# FPGA.net
KiCad netlist of a schematic drawn in Altium Designer
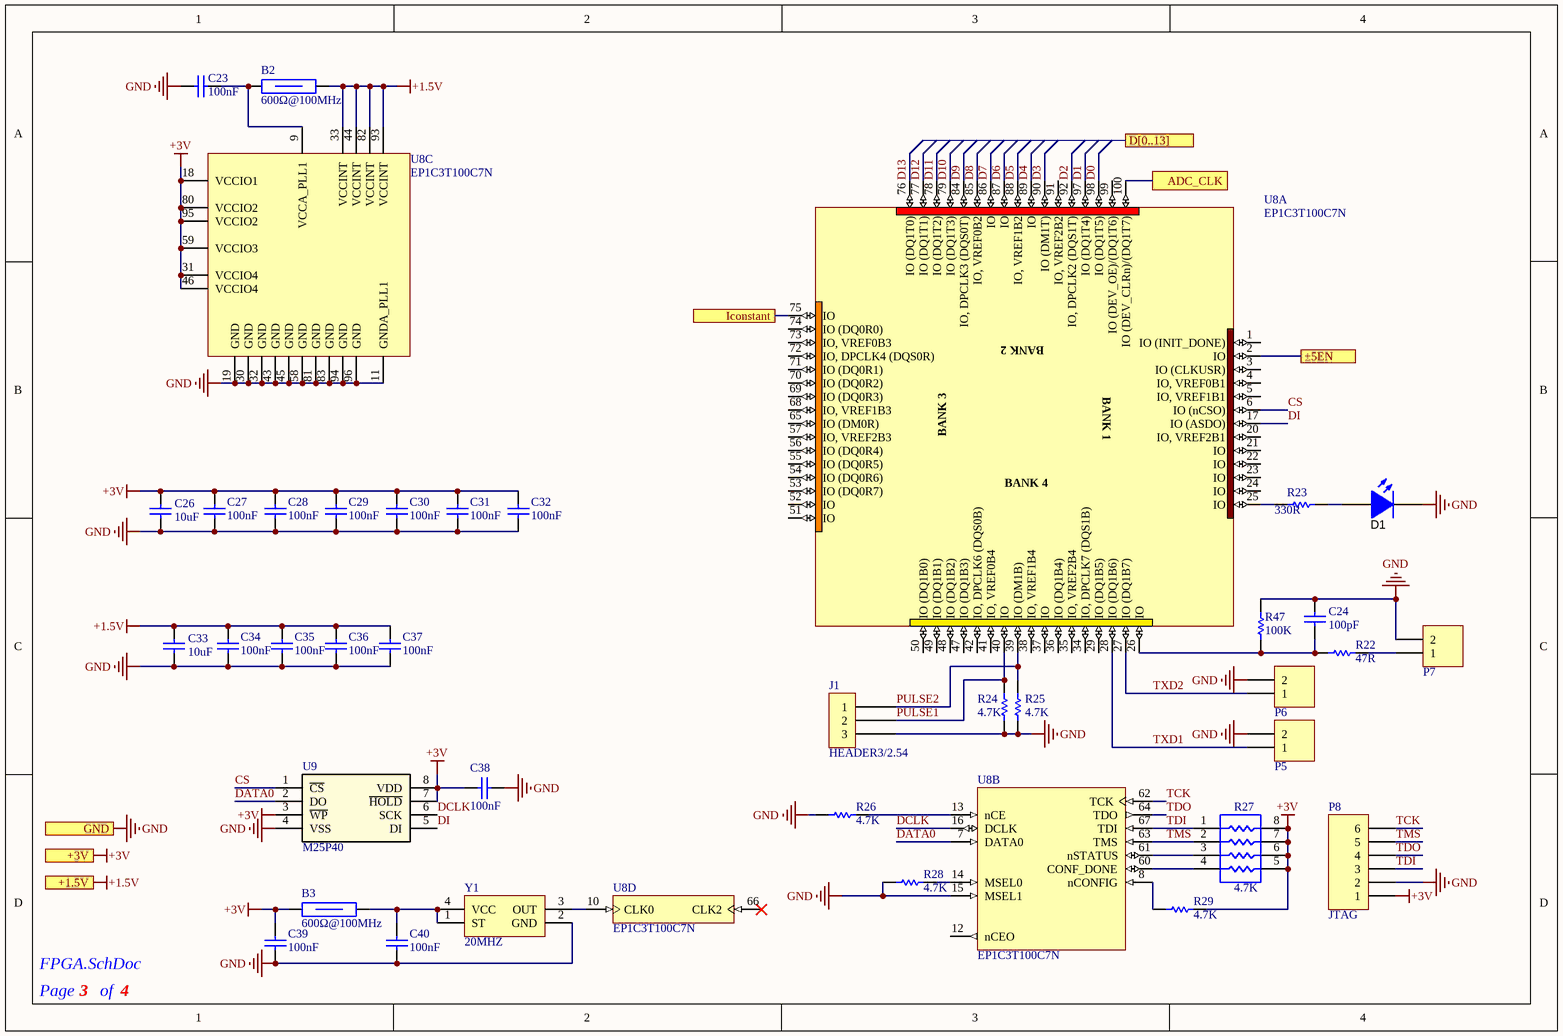
[diagram p0: FPGA.SchDoc]

(export (version "E")
  (design (tool "Eeschema 10.0.6"))
  (components
    (comp (ref "B2")
      (value "600Ω@100MHz")
      (footprint "R0805_L")
      (description "600Ω @ 100MHz \r\n线路数 1 \r\n额定电流（最大） 600mA \r\n直流电阻（DCR）（最大） 210mΩ")
      (libsource (lib "00Lib") (part "600Ω@100MHz"))
    )
    (comp (ref "B3")
      (value "600Ω@100MHz")
      (footprint "R0805_L")
      (description "600Ω @ 100MHz \r\n线路数 1 \r\n额定电流（最大） 600mA \r\n直流电阻（DCR）（最大） 210mΩ")
      (libsource (lib "00Lib") (part "600Ω@100MHz"))
    )
    (comp (ref "C23")
      (value "100nF")
      (footprint "R0603_C")
      (description "精度 ±10% \r\n容值 100nF \r\n额定电压 50V \r\n温漂系数（介质材料) X7R")
      (libsource (lib "00Lib") (part "100nF/0603/50V"))
    )
    (comp (ref "C24")
      (value "100pF")
      (footprint "R0603_C")
      (description "精度 ±5% \r\n容值 100pF \r\n额定电压 50V \r\n温漂系数（介质材料) C0G")
      (libsource (lib "00Lib") (part "100pF/0603/50V"))
    )
    (comp (ref "C26")
      (value "10uF")
      (footprint "R0805_C")
      (description "精度 ±10% \r\n容值 10uF \r\n额定电压 16V \r\n温漂系数（介质材料) X7R")
      (libsource (lib "00Lib") (part "10uF/0805/16V"))
    )
    (comp (ref "C27")
      (value "100nF")
      (footprint "R0603_C")
      (description "精度 ±10% \r\n容值 100nF \r\n额定电压 50V \r\n温漂系数（介质材料) X7R")
      (libsource (lib "00Lib") (part "100nF/0603/50V"))
    )
    (comp (ref "C28")
      (value "100nF")
      (footprint "R0603_C")
      (description "精度 ±10% \r\n容值 100nF \r\n额定电压 50V \r\n温漂系数（介质材料) X7R")
      (libsource (lib "00Lib") (part "100nF/0603/50V"))
    )
    (comp (ref "C29")
      (value "100nF")
      (footprint "R0603_C")
      (description "精度 ±10% \r\n容值 100nF \r\n额定电压 50V \r\n温漂系数（介质材料) X7R")
      (libsource (lib "00Lib") (part "100nF/0603/50V"))
    )
    (comp (ref "C30")
      (value "100nF")
      (footprint "R0603_C")
      (description "精度 ±10% \r\n容值 100nF \r\n额定电压 50V \r\n温漂系数（介质材料) X7R")
      (libsource (lib "00Lib") (part "100nF/0603/50V"))
    )
    (comp (ref "C31")
      (value "100nF")
      (footprint "R0603_C")
      (description "精度 ±10% \r\n容值 100nF \r\n额定电压 50V \r\n温漂系数（介质材料) X7R")
      (libsource (lib "00Lib") (part "100nF/0603/50V"))
    )
    (comp (ref "C32")
      (value "100nF")
      (footprint "R0603_C")
      (description "精度 ±10% \r\n容值 100nF \r\n额定电压 50V \r\n温漂系数（介质材料) X7R")
      (libsource (lib "00Lib") (part "100nF/0603/50V"))
    )
    (comp (ref "C33")
      (value "10uF")
      (footprint "R0805_C")
      (description "精度 ±10% \r\n容值 10uF \r\n额定电压 16V \r\n温漂系数（介质材料) X7R")
      (libsource (lib "00Lib") (part "10uF/0805/16V"))
    )
    (comp (ref "C34")
      (value "100nF")
      (footprint "R0603_C")
      (description "精度 ±10% \r\n容值 100nF \r\n额定电压 50V \r\n温漂系数（介质材料) X7R")
      (libsource (lib "00Lib") (part "100nF/0603/50V"))
    )
    (comp (ref "C35")
      (value "100nF")
      (footprint "R0603_C")
      (description "精度 ±10% \r\n容值 100nF \r\n额定电压 50V \r\n温漂系数（介质材料) X7R")
      (libsource (lib "00Lib") (part "100nF/0603/50V"))
    )
    (comp (ref "C36")
      (value "100nF")
      (footprint "R0603_C")
      (description "精度 ±10% \r\n容值 100nF \r\n额定电压 50V \r\n温漂系数（介质材料) X7R")
      (libsource (lib "00Lib") (part "100nF/0603/50V"))
    )
    (comp (ref "C37")
      (value "100nF")
      (footprint "R0603_C")
      (description "精度 ±10% \r\n容值 100nF \r\n额定电压 50V \r\n温漂系数（介质材料) X7R")
      (libsource (lib "00Lib") (part "100nF/0603/50V"))
    )
    (comp (ref "C38")
      (value "100nF")
      (footprint "R0603_C")
      (description "精度 ±10% \r\n容值 100nF \r\n额定电压 50V \r\n温漂系数（介质材料) X7R")
      (libsource (lib "00Lib") (part "100nF/0603/50V"))
    )
    (comp (ref "C39")
      (value "100nF")
      (footprint "R0603_C")
      (description "精度 ±10% \r\n容值 100nF \r\n额定电压 50V \r\n温漂系数（介质材料) X7R")
      (libsource (lib "00Lib") (part "100nF/0603/50V"))
    )
    (comp (ref "C40")
      (value "100nF")
      (footprint "R0603_C")
      (description "精度 ±10% \r\n容值 100nF \r\n额定电压 50V \r\n温漂系数（介质材料) X7R")
      (libsource (lib "00Lib") (part "100nF/0603/50V"))
    )
    (comp (ref "D1")
      (value "MHT192WDT-C2")
      (footprint "LED_0603_RED")
      (libsource (lib "00") (part "MHT192WDT-C2"))
    )
    (comp (ref "J1")
      (value "HEADER3/2.54")
      (footprint "SIP3/2.54")
      (description "3pin,单排,2.54mm间距")
      (libsource (lib "00Lib") (part "HEADER3/2.54"))
    )
    (comp (ref "P5")
      (value "Header 2")
      (footprint "CP1X2")
      (description "Header, 2-Pin")
      (libsource (lib "00Lib") (part "Header 2"))
    )
    (comp (ref "P6")
      (value "Header 2")
      (footprint "CP1X2")
      (description "Header, 2-Pin")
      (libsource (lib "00Lib") (part "Header 2"))
    )
    (comp (ref "P7")
      (value "Header 2")
      (footprint "CP1X2")
      (description "Header, 2-Pin")
      (libsource (lib "00Lib") (part "Header 2"))
    )
    (comp (ref "P8")
      (value "JTAG")
      (footprint "CP1X6")
      (description "Header, 6-Pin")
      (libsource (lib "00Lib") (part "Header 6"))
    )
    (comp (ref "R22")
      (value "47R")
      (footprint "R0603_R")
      (description "精度 ±1% \r\n温度系数 ±100ppm/℃ \r\n阻值 47Ω \r\n功率 0.1W")
      (libsource (lib "00Lib") (part "47R/0603"))
    )
    (comp (ref "R23")
      (value "330R")
      (footprint "R0603_R")
      (description "精度 ±1% \r\n温度系数 ±100ppm/℃ \r\n阻值 330Ω \r\n功率 0.1W")
      (libsource (lib "00Lib") (part "330R/0603"))
    )
    (comp (ref "R24")
      (value "4.7K")
      (footprint "R0603_R")
      (description "精度 ±1% \r\n阻值 4.7kΩ \r\n温度系数 ±100ppm/℃ \r\n功率 0.1W")
      (libsource (lib "00Lib") (part "4.7K/0603"))
    )
    (comp (ref "R25")
      (value "4.7K")
      (footprint "R0603_R")
      (description "精度 ±1% \r\n阻值 4.7kΩ \r\n温度系数 ±100ppm/℃ \r\n功率 0.1W")
      (libsource (lib "00Lib") (part "4.7K/0603"))
    )
    (comp (ref "R26")
      (value "4.7K")
      (footprint "R0603_R")
      (description "精度 ±1% \r\n阻值 4.7kΩ \r\n温度系数 ±100ppm/℃ \r\n功率 0.1W")
      (libsource (lib "00Lib") (part "4.7K/0603"))
    )
    (comp (ref "R27")
      (value "4.7K")
      (footprint "R0603X4")
      (description "4.7K \r\n电阻器数 4 \r\n精度 ±1% \r\n安装类型 表面贴装 \r\n每元件功率 1/16W \r\n温度系数 ±200ppm/℃")
      (libsource (lib "00Lib") (part "4.7K/0603X4"))
    )
    (comp (ref "R28")
      (value "4.7K")
      (footprint "R0603_R")
      (description "精度 ±1% \r\n阻值 4.7kΩ \r\n温度系数 ±100ppm/℃ \r\n功率 0.1W")
      (libsource (lib "00Lib") (part "4.7K/0603"))
    )
    (comp (ref "R29")
      (value "4.7K")
      (footprint "R0603_R")
      (description "精度 ±1% \r\n阻值 4.7kΩ \r\n温度系数 ±100ppm/℃ \r\n功率 0.1W")
      (libsource (lib "00Lib") (part "4.7K/0603"))
    )
    (comp (ref "R47")
      (value "100K")
      (footprint "R0603_R")
      (description "精度 ±1% \r\n阻值 100kΩ \r\n温度系数 ±100ppm/℃ \r\n功率 0.1W")
      (libsource (lib "00Lib") (part "100K/0603"))
    )
    (comp (ref "U8")
      (value "EP1C3T100C7N")
      (footprint "TQFP100")
      (description "Cyclone Family, 1.5V FPGA, 65 I/O Pins, 1 x PLL, Commercial Grade, Speed Grade 7, Pb-Free")
      (fields (field (name "MANUFACTURER") "INTEL"))
      (libsource (lib "00") (part "EP1C3T100C7N"))
    )
    (comp (ref "U9")
      (value "M25P40")
      (footprint "SOP-8_150mil")
      (description "FLASH - NOR\r\n4Mb（512K x 8）\r\nSPI\r\n电压 - 供电\r\n2.3V ~ 3.6V\r\n工作温度\r\n-40°C ~ 85°C（TA）")
      (libsource (lib "00Lib") (part "M25P40"))
    )
    (comp (ref "Y1")
      (value "20MHZ")
      (footprint "SMD-3225")
      (description "工作电压 2.7V ~ 3.6V \r\n主频 20MHz \r\n频率稳定度 ±50ppm \r\n工作温度 -40℃~85℃")
      (libsource (lib "00Lib") (part "SG-310SCF 20MHZ L"))
    )
  )
  (nets
    (net (code "1") (name "+1.5V") (class "Default")
      (node (ref "B2") (pin "2") (pinfunction "2_2") (pintype "passive"))
      (node (ref "C33") (pin "1") (pinfunction "1_1") (pintype "passive"))
      (node (ref "C34") (pin "2") (pinfunction "2_2") (pintype "passive"))
      (node (ref "C35") (pin "2") (pinfunction "2_2") (pintype "passive"))
      (node (ref "C36") (pin "2") (pinfunction "2_2") (pintype "passive"))
      (node (ref "C37") (pin "2") (pinfunction "2_2") (pintype "passive"))
      (node (ref "U8") (pin "33") (pinfunction "VCCINT_33") (pintype "power_in"))
      (node (ref "U8") (pin "44") (pinfunction "VCCINT_44") (pintype "power_in"))
      (node (ref "U8") (pin "82") (pinfunction "VCCINT_82") (pintype "power_in"))
      (node (ref "U8") (pin "93") (pinfunction "VCCINT_93") (pintype "power_in"))
    )
    (net (code "2") (name "+3V") (class "Default")
      (node (ref "B3") (pin "1") (pinfunction "1_1") (pintype "passive"))
      (node (ref "C26") (pin "2") (pinfunction "2_2") (pintype "passive"))
      (node (ref "C27") (pin "2") (pinfunction "2_2") (pintype "passive"))
      (node (ref "C28") (pin "2") (pinfunction "2_2") (pintype "passive"))
      (node (ref "C29") (pin "2") (pinfunction "2_2") (pintype "passive"))
      (node (ref "C30") (pin "2") (pinfunction "2_2") (pintype "passive"))
      (node (ref "C31") (pin "2") (pinfunction "2_2") (pintype "passive"))
      (node (ref "C32") (pin "2") (pinfunction "2_2") (pintype "passive"))
      (node (ref "C38") (pin "2") (pinfunction "2_2") (pintype "passive"))
      (node (ref "C39") (pin "2") (pinfunction "2_2") (pintype "passive"))
      (node (ref "P8") (pin "1") (pinfunction "1_1") (pintype "passive"))
      (node (ref "R27") (pin "5") (pinfunction "5_5") (pintype "passive"))
      (node (ref "R27") (pin "6") (pinfunction "6_6") (pintype "passive"))
      (node (ref "R27") (pin "7") (pinfunction "7_7") (pintype "passive"))
      (node (ref "R27") (pin "8") (pinfunction "8_8") (pintype "passive"))
      (node (ref "R29") (pin "1") (pinfunction "1_1") (pintype "passive"))
      (node (ref "U8") (pin "18") (pinfunction "VCCIO1_18") (pintype "power_in"))
      (node (ref "U8") (pin "31") (pinfunction "VCCIO4_31") (pintype "power_in"))
      (node (ref "U8") (pin "46") (pinfunction "VCCIO4_46") (pintype "power_in"))
      (node (ref "U8") (pin "59") (pinfunction "VCCIO3_59") (pintype "power_in"))
      (node (ref "U8") (pin "80") (pinfunction "VCCIO2_80") (pintype "power_in"))
      (node (ref "U8") (pin "95") (pinfunction "VCCIO2_95") (pintype "power_in"))
      (node (ref "U9") (pin "3") (pinfunction "~{WP}_3") (pintype "power_in"))
      (node (ref "U9") (pin "7") (pinfunction "~{HOLD}_7") (pintype "passive"))
      (node (ref "U9") (pin "8") (pinfunction "VDD_8") (pintype "passive"))
    )
    (net (code "3") (name "/ADC_CLK") (class "Default")
      (node (ref "U8") (pin "100") (pinfunction "IO_(DEV_CLRn)/(DQ1T7)_100") (pintype "bidirectional"))
    )
    (net (code "4") (name "/CS") (class "Default")
      (node (ref "U8") (pin "6") (pinfunction "IO_(nCSO)_6") (pintype "bidirectional"))
      (node (ref "U9") (pin "1") (pinfunction "~{CS}_1") (pintype "power_in"))
    )
    (net (code "5") (name "/D0") (class "Default")
      (node (ref "U8") (pin "98") (pinfunction "IO_(DQ1T5)_98") (pintype "bidirectional"))
    )
    (net (code "6") (name "/D1") (class "Default")
      (node (ref "U8") (pin "97") (pinfunction "IO_(DQ1T4)_97") (pintype "bidirectional"))
    )
    (net (code "7") (name "/D2") (class "Default")
      (node (ref "U8") (pin "92") (pinfunction "IO,_DPCLK2_(DQS1T)_92") (pintype "bidirectional"))
    )
    (net (code "8") (name "/D3") (class "Default")
      (node (ref "U8") (pin "90") (pinfunction "IO_(DM1T)_90") (pintype "bidirectional"))
    )
    (net (code "9") (name "/D4") (class "Default")
      (node (ref "U8") (pin "89") (pinfunction "IO_89") (pintype "bidirectional"))
    )
    (net (code "10") (name "/D5") (class "Default")
      (node (ref "U8") (pin "88") (pinfunction "IO,_VREF1B2_88") (pintype "bidirectional"))
    )
    (net (code "11") (name "/D6") (class "Default")
      (node (ref "U8") (pin "87") (pinfunction "IO_87") (pintype "bidirectional"))
    )
    (net (code "12") (name "/D7") (class "Default")
      (node (ref "U8") (pin "86") (pinfunction "IO_86") (pintype "bidirectional"))
    )
    (net (code "13") (name "/D8") (class "Default")
      (node (ref "U8") (pin "85") (pinfunction "IO,_VREF0B2_85") (pintype "bidirectional"))
    )
    (net (code "14") (name "/D9") (class "Default")
      (node (ref "U8") (pin "84") (pinfunction "IO,_DPCLK3_(DQS0T)_84") (pintype "bidirectional"))
    )
    (net (code "15") (name "/D10") (class "Default")
      (node (ref "U8") (pin "79") (pinfunction "IO_(DQ1T3)_79") (pintype "bidirectional"))
    )
    (net (code "16") (name "/D11") (class "Default")
      (node (ref "U8") (pin "78") (pinfunction "IO_(DQ1T2)_78") (pintype "bidirectional"))
    )
    (net (code "17") (name "/D12") (class "Default")
      (node (ref "U8") (pin "77") (pinfunction "IO_(DQ1T1)_77") (pintype "bidirectional"))
    )
    (net (code "18") (name "/D13") (class "Default")
      (node (ref "U8") (pin "76") (pinfunction "IO_(DQ1T0)_76") (pintype "bidirectional"))
    )
    (net (code "19") (name "/DATA0") (class "Default")
      (node (ref "U8") (pin "7") (pinfunction "DATA0_7") (pintype "input"))
      (node (ref "U9") (pin "2") (pinfunction "DO_2") (pintype "power_in"))
    )
    (net (code "20") (name "/DCLK") (class "Default")
      (node (ref "U8") (pin "16") (pinfunction "DCLK_16") (pintype "bidirectional"))
      (node (ref "U9") (pin "6") (pinfunction "SCK_6") (pintype "passive"))
    )
    (net (code "21") (name "/DI") (class "Default")
      (node (ref "U8") (pin "17") (pinfunction "IO_(ASDO)_17") (pintype "bidirectional"))
      (node (ref "U9") (pin "5") (pinfunction "DI_5") (pintype "passive"))
    )
    (net (code "23") (name "/Iconstant") (class "Default")
      (node (ref "U8") (pin "75") (pinfunction "IO_75") (pintype "bidirectional"))
    )
    (net (code "24") (name "/PULSE1") (class "Default")
      (node (ref "J1") (pin "2") (pinfunction "2_2") (pintype "passive"))
      (node (ref "R24") (pin "1") (pinfunction "1_1") (pintype "passive"))
      (node (ref "U8") (pin "40") (pinfunction "IO_40") (pintype "bidirectional"))
    )
    (net (code "25") (name "/PULSE2") (class "Default")
      (node (ref "J1") (pin "1") (pinfunction "1_1") (pintype "passive"))
      (node (ref "R25") (pin "1") (pinfunction "1_1") (pintype "passive"))
      (node (ref "U8") (pin "39") (pinfunction "IO_(DM1B)_39") (pintype "bidirectional"))
    )
    (net (code "26") (name "/TCK") (class "Default")
      (node (ref "P8") (pin "6") (pinfunction "6_6") (pintype "passive"))
      (node (ref "U8") (pin "62") (pinfunction "TCK_62") (pintype "input"))
    )
    (net (code "27") (name "/TDI") (class "Default")
      (node (ref "P8") (pin "3") (pinfunction "3_3") (pintype "passive"))
      (node (ref "R27") (pin "1") (pinfunction "1_1") (pintype "passive"))
      (node (ref "U8") (pin "67") (pinfunction "TDI_67") (pintype "input"))
    )
    (net (code "28") (name "/TDO") (class "Default")
      (node (ref "P8") (pin "4") (pinfunction "4_4") (pintype "passive"))
      (node (ref "U8") (pin "64") (pinfunction "TDO_64") (pintype "output"))
    )
    (net (code "29") (name "/TMS") (class "Default")
      (node (ref "P8") (pin "5") (pinfunction "5_5") (pintype "passive"))
      (node (ref "R27") (pin "2") (pinfunction "2_2") (pintype "passive"))
      (node (ref "U8") (pin "63") (pinfunction "TMS_63") (pintype "input"))
    )
    (net (code "30") (name "/TXD1") (class "Default")
      (node (ref "P5") (pin "1") (pinfunction "1_1") (pintype "passive"))
      (node (ref "U8") (pin "28") (pinfunction "IO_(DQ1B6)_28") (pintype "bidirectional"))
    )
    (net (code "31") (name "/TXD2") (class "Default")
      (node (ref "P6") (pin "1") (pinfunction "1_1") (pintype "passive"))
      (node (ref "U8") (pin "27") (pinfunction "IO_(DQ1B7)_27") (pintype "bidirectional"))
    )
    (net (code "32") (name "/±5EN") (class "Default")
      (node (ref "U8") (pin "2") (pinfunction "IO_2") (pintype "bidirectional"))
    )
    (net (code "33") (name "GND") (class "Default")
      (node (ref "C23") (pin "2") (pinfunction "2_2") (pintype "passive"))
      (node (ref "C24") (pin "1") (pinfunction "1_1") (pintype "passive"))
      (node (ref "C26") (pin "1") (pinfunction "1_1") (pintype "passive"))
      (node (ref "C27") (pin "1") (pinfunction "1_1") (pintype "passive"))
      (node (ref "C28") (pin "1") (pinfunction "1_1") (pintype "passive"))
      (node (ref "C29") (pin "1") (pinfunction "1_1") (pintype "passive"))
      (node (ref "C30") (pin "1") (pinfunction "1_1") (pintype "passive"))
      (node (ref "C31") (pin "1") (pinfunction "1_1") (pintype "passive"))
      (node (ref "C32") (pin "1") (pinfunction "1_1") (pintype "passive"))
      (node (ref "C33") (pin "2") (pinfunction "2_2") (pintype "passive"))
      (node (ref "C34") (pin "1") (pinfunction "1_1") (pintype "passive"))
      (node (ref "C35") (pin "1") (pinfunction "1_1") (pintype "passive"))
      (node (ref "C36") (pin "1") (pinfunction "1_1") (pintype "passive"))
      (node (ref "C37") (pin "1") (pinfunction "1_1") (pintype "passive"))
      (node (ref "C38") (pin "1") (pinfunction "1_1") (pintype "passive"))
      (node (ref "C39") (pin "1") (pinfunction "1_1") (pintype "passive"))
      (node (ref "C40") (pin "1") (pinfunction "1_1") (pintype "passive"))
      (node (ref "D1") (pin "2") (pinfunction "K_2") (pintype "passive"))
      (node (ref "J1") (pin "3") (pinfunction "3_3") (pintype "passive"))
      (node (ref "P5") (pin "2") (pinfunction "2_2") (pintype "passive"))
      (node (ref "P6") (pin "2") (pinfunction "2_2") (pintype "passive"))
      (node (ref "P7") (pin "2") (pinfunction "2_2") (pintype "passive"))
      (node (ref "P8") (pin "2") (pinfunction "2_2") (pintype "passive"))
      (node (ref "R24") (pin "2") (pinfunction "2_2") (pintype "passive"))
      (node (ref "R25") (pin "2") (pinfunction "2_2") (pintype "passive"))
      (node (ref "R26") (pin "2") (pinfunction "2_2") (pintype "passive"))
      (node (ref "R28") (pin "1") (pinfunction "1_1") (pintype "passive"))
      (node (ref "R47") (pin "1") (pinfunction "1_1") (pintype "passive"))
      (node (ref "U8") (pin "11") (pinfunction "GNDA_PLL1_11") (pintype "power_in"))
      (node (ref "U8") (pin "15") (pinfunction "MSEL1_15") (pintype "input"))
      (node (ref "U8") (pin "19") (pinfunction "GND_19") (pintype "power_in"))
      (node (ref "U8") (pin "30") (pinfunction "GND_30") (pintype "power_in"))
      (node (ref "U8") (pin "32") (pinfunction "GND_32") (pintype "power_in"))
      (node (ref "U8") (pin "43") (pinfunction "GND_43") (pintype "power_in"))
      (node (ref "U8") (pin "45") (pinfunction "GND_45") (pintype "power_in"))
      (node (ref "U8") (pin "58") (pinfunction "GND_58") (pintype "power_in"))
      (node (ref "U8") (pin "81") (pinfunction "GND_81") (pintype "power_in"))
      (node (ref "U8") (pin "83") (pinfunction "GND_83") (pintype "power_in"))
      (node (ref "U8") (pin "94") (pinfunction "GND_94") (pintype "power_in"))
      (node (ref "U8") (pin "96") (pinfunction "GND_96") (pintype "power_in"))
      (node (ref "U9") (pin "4") (pinfunction "VSS_4") (pintype "passive"))
      (node (ref "Y1") (pin "2") (pinfunction "GND_2") (pintype "power_in"))
    )
    (net (code "34") (name "Net-(C24-Pad2)") (class "Default")
      (node (ref "C24") (pin "2") (pinfunction "2_2") (pintype "passive"))
      (node (ref "R22") (pin "1") (pinfunction "1_1") (pintype "passive"))
      (node (ref "R47") (pin "2") (pinfunction "2_2") (pintype "passive"))
      (node (ref "U8") (pin "26") (pinfunction "IO_26") (pintype "bidirectional"))
    )
    (net (code "35") (name "Net-(D1-A)") (class "Default")
      (node (ref "D1") (pin "1") (pinfunction "A_1") (pintype "passive"))
      (node (ref "R23") (pin "2") (pinfunction "2_2") (pintype "passive"))
    )
    (net (code "36") (name "Net-(P7-Pad1)") (class "Default")
      (node (ref "P7") (pin "1") (pinfunction "1_1") (pintype "passive"))
      (node (ref "R22") (pin "2") (pinfunction "2_2") (pintype "passive"))
    )
    (net (code "37") (name "Net-(R23-Pad1)") (class "Default")
      (node (ref "R23") (pin "1") (pinfunction "1_1") (pintype "passive"))
      (node (ref "U8") (pin "25") (pinfunction "IO_25") (pintype "bidirectional"))
    )
    (net (code "38") (name "Net-(U8B-CONF_DONE)") (class "Default")
      (node (ref "R27") (pin "4") (pinfunction "4_4") (pintype "passive"))
      (node (ref "U8") (pin "60") (pinfunction "CONF_DONE_60") (pintype "bidirectional"))
    )
    (net (code "39") (name "Net-(U8B-MSEL0)") (class "Default")
      (node (ref "R28") (pin "2") (pinfunction "2_2") (pintype "passive"))
      (node (ref "U8") (pin "14") (pinfunction "MSEL0_14") (pintype "input"))
    )
    (net (code "40") (name "Net-(U8B-nCE)") (class "Default")
      (node (ref "R26") (pin "1") (pinfunction "1_1") (pintype "passive"))
      (node (ref "U8") (pin "13") (pinfunction "nCE_13") (pintype "input"))
    )
    (net (code "41") (name "Net-(U8B-nCONFIG)") (class "Default")
      (node (ref "R29") (pin "2") (pinfunction "2_2") (pintype "passive"))
      (node (ref "U8") (pin "8") (pinfunction "nCONFIG_8") (pintype "input"))
    )
    (net (code "42") (name "Net-(U8B-nSTATUS)") (class "Default")
      (node (ref "R27") (pin "3") (pinfunction "3_3") (pintype "passive"))
      (node (ref "U8") (pin "61") (pinfunction "nSTATUS_61") (pintype "bidirectional"))
    )
    (net (code "43") (name "Net-(U8C-VCCA_PLL1)") (class "Default")
      (node (ref "B2") (pin "1") (pinfunction "1_1") (pintype "passive"))
      (node (ref "C23") (pin "1") (pinfunction "1_1") (pintype "passive"))
      (node (ref "U8") (pin "9") (pinfunction "VCCA_PLL1_9") (pintype "power_in"))
    )
    (net (code "44") (name "Net-(U8D-CLK0)") (class "Default")
      (node (ref "U8") (pin "10") (pinfunction "CLK0_10") (pintype "input"))
      (node (ref "Y1") (pin "3") (pinfunction "OUT_3") (pintype "passive"))
    )
    (net (code "45") (name "Net-(Y1-ST)") (class "Default")
      (node (ref "B3") (pin "2") (pinfunction "2_2") (pintype "passive"))
      (node (ref "C40") (pin "2") (pinfunction "2_2") (pintype "passive"))
      (node (ref "Y1") (pin "1") (pinfunction "ST_1") (pintype "passive"))
      (node (ref "Y1") (pin "4") (pinfunction "VCC_4") (pintype "power_in"))
    )
    (net (code "46") (name "unconnected-(U8A-IO,_DPCLK4_(DQS0R)-Pad72)") (class "Default")
      (node (ref "U8") (pin "72") (pinfunction "IO,_DPCLK4_(DQS0R)_72") (pintype "bidirectional"))
    )
    (net (code "47") (name "unconnected-(U8A-IO,_DPCLK6_(DQS0B)-Pad42)") (class "Default")
      (node (ref "U8") (pin "42") (pinfunction "IO,_DPCLK6_(DQS0B)_42") (pintype "bidirectional"))
    )
    (net (code "48") (name "unconnected-(U8A-IO,_DPCLK7_(DQS1B)-Pad34)") (class "Default")
      (node (ref "U8") (pin "34") (pinfunction "IO,_DPCLK7_(DQS1B)_34") (pintype "bidirectional"))
    )
    (net (code "49") (name "unconnected-(U8A-IO,_VREF0B1-Pad4)") (class "Default")
      (node (ref "U8") (pin "4") (pinfunction "IO,_VREF0B1_4") (pintype "bidirectional"))
    )
    (net (code "50") (name "unconnected-(U8A-IO,_VREF0B3-Pad73)") (class "Default")
      (node (ref "U8") (pin "73") (pinfunction "IO,_VREF0B3_73") (pintype "bidirectional"))
    )
    (net (code "51") (name "unconnected-(U8A-IO,_VREF0B4-Pad41)") (class "Default")
      (node (ref "U8") (pin "41") (pinfunction "IO,_VREF0B4_41") (pintype "bidirectional"))
    )
    (net (code "52") (name "unconnected-(U8A-IO,_VREF1B1-Pad5)") (class "Default")
      (node (ref "U8") (pin "5") (pinfunction "IO,_VREF1B1_5") (pintype "bidirectional"))
    )
    (net (code "53") (name "unconnected-(U8A-IO,_VREF1B3-Pad68)") (class "Default")
      (node (ref "U8") (pin "68") (pinfunction "IO,_VREF1B3_68") (pintype "bidirectional"))
    )
    (net (code "54") (name "unconnected-(U8A-IO,_VREF1B4-Pad38)") (class "Default")
      (node (ref "U8") (pin "38") (pinfunction "IO,_VREF1B4_38") (pintype "bidirectional"))
    )
    (net (code "55") (name "unconnected-(U8A-IO,_VREF2B1-Pad20)") (class "Default")
      (node (ref "U8") (pin "20") (pinfunction "IO,_VREF2B1_20") (pintype "bidirectional"))
    )
    (net (code "56") (name "unconnected-(U8A-IO,_VREF2B2-Pad91)") (class "Default")
      (node (ref "U8") (pin "91") (pinfunction "IO,_VREF2B2_91") (pintype "bidirectional"))
    )
    (net (code "57") (name "unconnected-(U8A-IO,_VREF2B3-Pad57)") (class "Default")
      (node (ref "U8") (pin "57") (pinfunction "IO,_VREF2B3_57") (pintype "bidirectional"))
    )
    (net (code "58") (name "unconnected-(U8A-IO,_VREF2B4-Pad35)") (class "Default")
      (node (ref "U8") (pin "35") (pinfunction "IO,_VREF2B4_35") (pintype "bidirectional"))
    )
    (net (code "59") (name "unconnected-(U8A-IO-Pad21)") (class "Default")
      (node (ref "U8") (pin "21") (pinfunction "IO_21") (pintype "bidirectional"))
    )
    (net (code "60") (name "unconnected-(U8A-IO-Pad22)") (class "Default")
      (node (ref "U8") (pin "22") (pinfunction "IO_22") (pintype "bidirectional"))
    )
    (net (code "61") (name "unconnected-(U8A-IO-Pad23)") (class "Default")
      (node (ref "U8") (pin "23") (pinfunction "IO_23") (pintype "bidirectional"))
    )
    (net (code "62") (name "unconnected-(U8A-IO-Pad24)") (class "Default")
      (node (ref "U8") (pin "24") (pinfunction "IO_24") (pintype "bidirectional"))
    )
    (net (code "63") (name "unconnected-(U8A-IO-Pad37)") (class "Default")
      (node (ref "U8") (pin "37") (pinfunction "IO_37") (pintype "bidirectional"))
    )
    (net (code "64") (name "unconnected-(U8A-IO-Pad51)") (class "Default")
      (node (ref "U8") (pin "51") (pinfunction "IO_51") (pintype "bidirectional"))
    )
    (net (code "65") (name "unconnected-(U8A-IO-Pad52)") (class "Default")
      (node (ref "U8") (pin "52") (pinfunction "IO_52") (pintype "bidirectional"))
    )
    (net (code "66") (name "unconnected-(U8A-IO_(CLKUSR)-Pad3)") (class "Default")
      (node (ref "U8") (pin "3") (pinfunction "IO_(CLKUSR)_3") (pintype "bidirectional"))
    )
    (net (code "67") (name "unconnected-(U8A-IO_(DEV_OE){slash}(DQ1T6)-Pad99)") (class "Default")
      (node (ref "U8") (pin "99") (pinfunction "IO_(DEV_OE)/(DQ1T6)_99") (pintype "bidirectional"))
    )
    (net (code "68") (name "unconnected-(U8A-IO_(DM0R)-Pad65)") (class "Default")
      (node (ref "U8") (pin "65") (pinfunction "IO_(DM0R)_65") (pintype "bidirectional"))
    )
    (net (code "69") (name "unconnected-(U8A-IO_(DQ0R0)-Pad74)") (class "Default")
      (node (ref "U8") (pin "74") (pinfunction "IO_(DQ0R0)_74") (pintype "bidirectional"))
    )
    (net (code "70") (name "unconnected-(U8A-IO_(DQ0R1)-Pad71)") (class "Default")
      (node (ref "U8") (pin "71") (pinfunction "IO_(DQ0R1)_71") (pintype "bidirectional"))
    )
    (net (code "71") (name "unconnected-(U8A-IO_(DQ0R2)-Pad70)") (class "Default")
      (node (ref "U8") (pin "70") (pinfunction "IO_(DQ0R2)_70") (pintype "bidirectional"))
    )
    (net (code "72") (name "unconnected-(U8A-IO_(DQ0R3)-Pad69)") (class "Default")
      (node (ref "U8") (pin "69") (pinfunction "IO_(DQ0R3)_69") (pintype "bidirectional"))
    )
    (net (code "73") (name "unconnected-(U8A-IO_(DQ0R4)-Pad56)") (class "Default")
      (node (ref "U8") (pin "56") (pinfunction "IO_(DQ0R4)_56") (pintype "bidirectional"))
    )
    (net (code "74") (name "unconnected-(U8A-IO_(DQ0R5)-Pad55)") (class "Default")
      (node (ref "U8") (pin "55") (pinfunction "IO_(DQ0R5)_55") (pintype "bidirectional"))
    )
    (net (code "75") (name "unconnected-(U8A-IO_(DQ0R6)-Pad54)") (class "Default")
      (node (ref "U8") (pin "54") (pinfunction "IO_(DQ0R6)_54") (pintype "bidirectional"))
    )
    (net (code "76") (name "unconnected-(U8A-IO_(DQ0R7)-Pad53)") (class "Default")
      (node (ref "U8") (pin "53") (pinfunction "IO_(DQ0R7)_53") (pintype "bidirectional"))
    )
    (net (code "77") (name "unconnected-(U8A-IO_(DQ1B0)-Pad50)") (class "Default")
      (node (ref "U8") (pin "50") (pinfunction "IO_(DQ1B0)_50") (pintype "bidirectional"))
    )
    (net (code "78") (name "unconnected-(U8A-IO_(DQ1B1)-Pad49)") (class "Default")
      (node (ref "U8") (pin "49") (pinfunction "IO_(DQ1B1)_49") (pintype "bidirectional"))
    )
    (net (code "79") (name "unconnected-(U8A-IO_(DQ1B2)-Pad48)") (class "Default")
      (node (ref "U8") (pin "48") (pinfunction "IO_(DQ1B2)_48") (pintype "bidirectional"))
    )
    (net (code "80") (name "unconnected-(U8A-IO_(DQ1B3)-Pad47)") (class "Default")
      (node (ref "U8") (pin "47") (pinfunction "IO_(DQ1B3)_47") (pintype "bidirectional"))
    )
    (net (code "81") (name "unconnected-(U8A-IO_(DQ1B4)-Pad36)") (class "Default")
      (node (ref "U8") (pin "36") (pinfunction "IO_(DQ1B4)_36") (pintype "bidirectional"))
    )
    (net (code "82") (name "unconnected-(U8A-IO_(DQ1B5)-Pad29)") (class "Default")
      (node (ref "U8") (pin "29") (pinfunction "IO_(DQ1B5)_29") (pintype "bidirectional"))
    )
    (net (code "83") (name "unconnected-(U8A-IO_(INIT_DONE)-Pad1)") (class "Default")
      (node (ref "U8") (pin "1") (pinfunction "IO_(INIT_DONE)_1") (pintype "bidirectional"))
    )
    (net (code "84") (name "unconnected-(U8B-nCEO-Pad12)") (class "Default")
      (node (ref "U8") (pin "12") (pinfunction "nCEO_12") (pintype "output"))
    )
    (net (code "85") (name "unconnected-(U8D-CLK2-Pad66)") (class "Default")
      (node (ref "U8") (pin "66") (pinfunction "CLK2_66") (pintype "input+no_connect"))
    )
  )
)
